# ESP32-Mini-Matrix-Shield-DMA.net
KiCad netlist of a schematic drawn in EAGLE
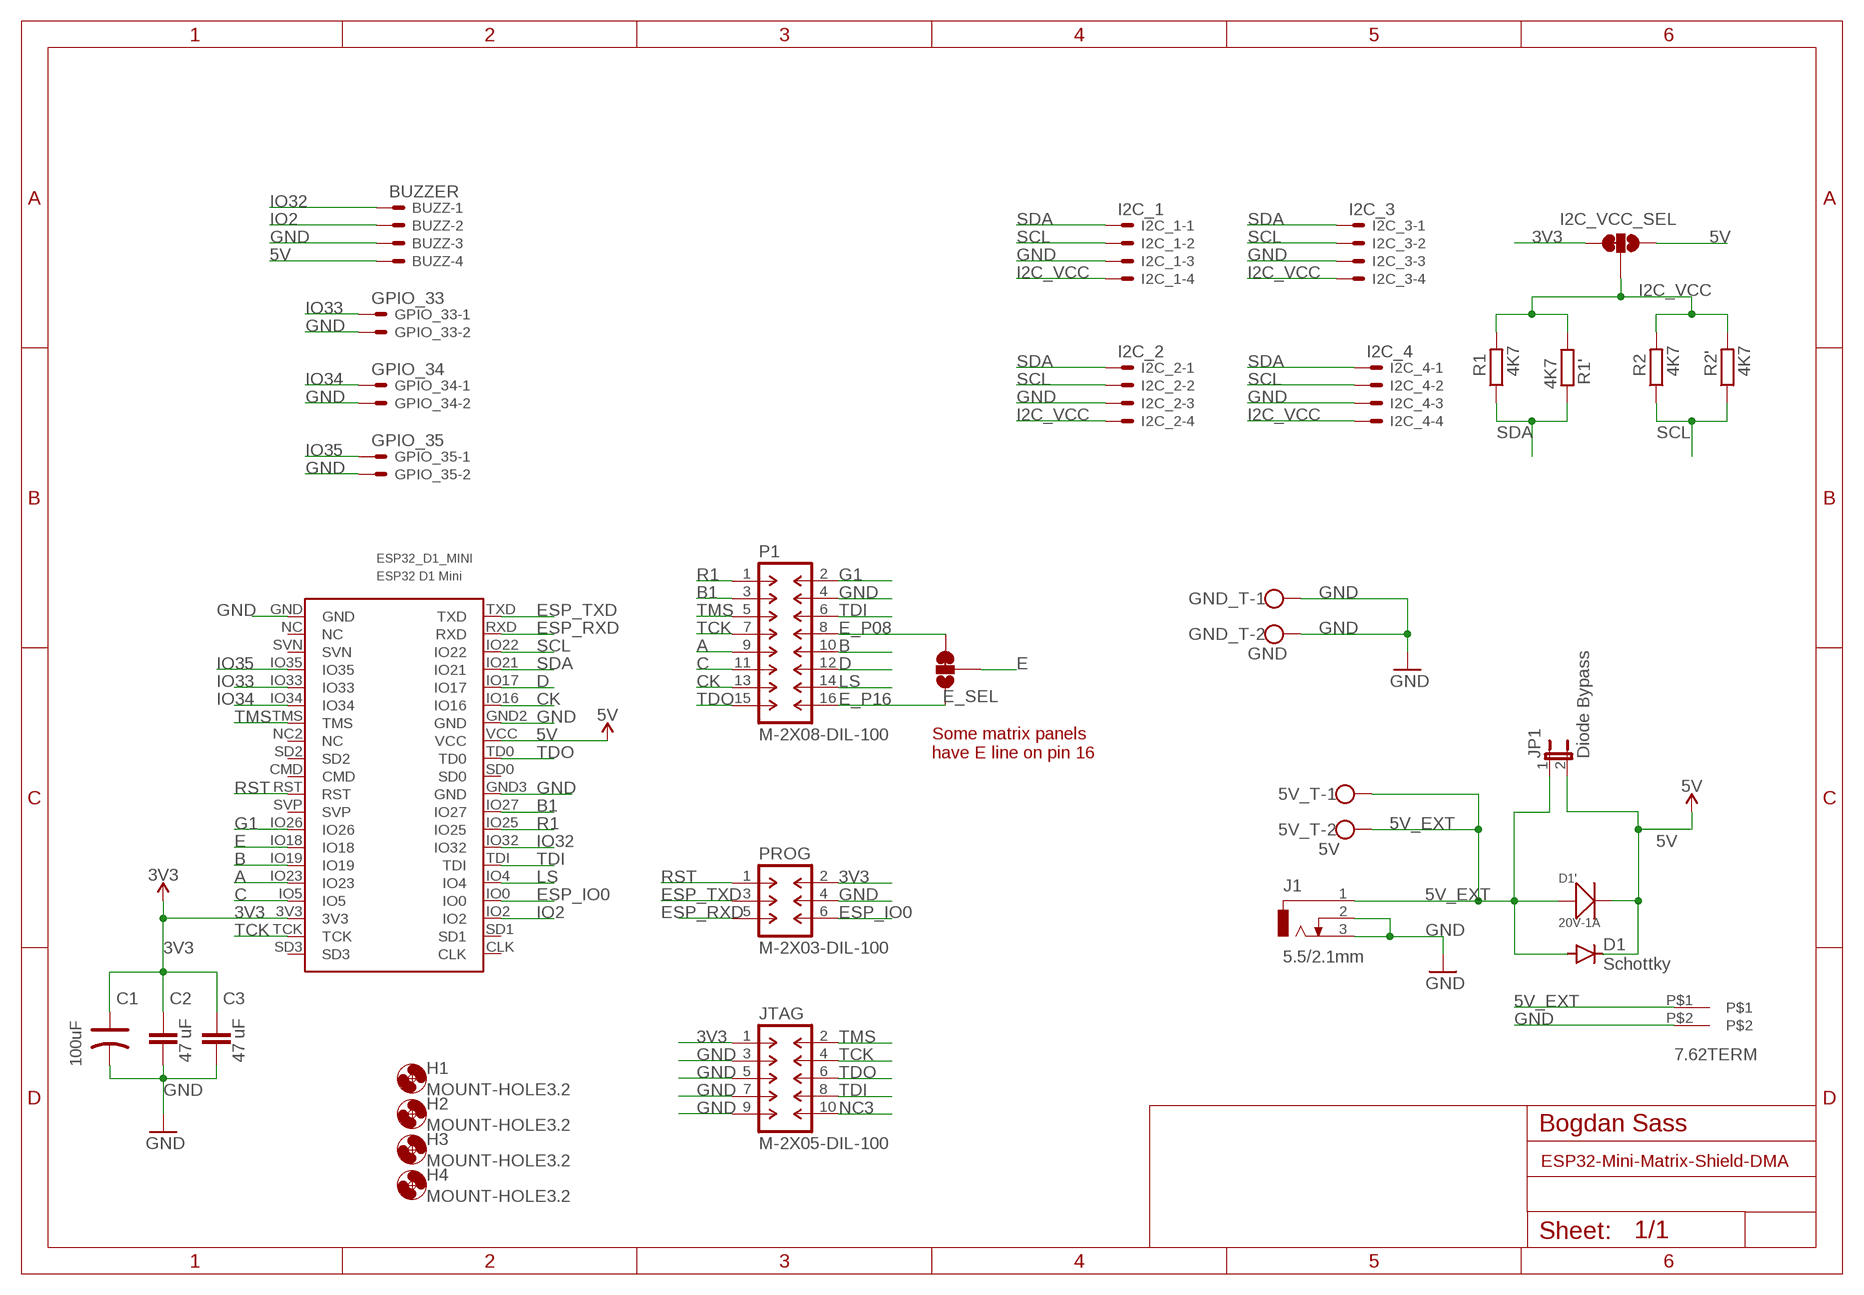
[diagram p0: schematic, sheet 1]

(export (version "E")
  (design (tool "Eeschema 10.0.6"))
  (components
    (comp (ref "5V_T")
      (value "5V")
      (footprint "eagle-import:W237-102")
      (fields (field (name "MPN") "237-102"))
      (libsource (lib "eagle-import") (part "W237-102"))
    )
    (comp (ref "BUZZ")
      (value "BUZZER")
      (footprint "eagle-import:JST-XH-04-PACKAGE-LONG-PAD")
      (libsource (lib "eagle-import") (part "JST-XH-04-PIN-LONG-PAD"))
    )
    (comp (ref "C1")
      (value "100uF")
      (footprint "eagle-import:PC-D5.3MM")
      (fields (field (name "MPN") "KS 100uF/16V"))
      (libsource (lib "eagle-import") (part "DIP-ALUMINUM-47UF-16V(D5-H7MM)"))
    )
    (comp (ref "C2")
      (value "47 uF")
      (footprint "eagle-import:0805-CAP-LARGEPADS")
      (libsource (lib "eagle-import") (part "CAP0805-CAP-LARGEPADS"))
    )
    (comp (ref "C3")
      (value "47 uF")
      (footprint "eagle-import:0805-CAP-LARGEPADS")
      (libsource (lib "eagle-import") (part "CAP0805-CAP-LARGEPADS"))
    )
    (comp (ref "D1")
      (value "Schottky")
      (footprint "eagle-import:DO41-10")
      (libsource (lib "eagle-import") (part "1N4004"))
    )
    (comp (ref "D1'")
      (value "20V-1A")
      (footprint "eagle-import:SOD-123")
      (fields (field (name "MPN") "B5819W"))
      (libsource (lib "eagle-import") (part "SMD-DIODE-SCHOTTKY-20V-1A(SOD-123)"))
    )
    (comp (ref "ESP32_D1_MINI")
      (value "ESP32 D1 Mini")
      (footprint "eagle-import:MH-ET_ESP32_D1_MINI")
      (libsource (lib "eagle-import") (part "MH-ET_ESP32_D1_MINI"))
    )
    (comp (ref "E_SEL")
      (value "JUMPER-SMT_3_1-NC_TRACE_SILK")
      (footprint "eagle-import:SMT-JUMPER_3_1-NC_TRACE_SILK")
      (libsource (lib "eagle-import") (part "JUMPER-SMT_3_1-NC_TRACE_SILK"))
    )
    (comp (ref "GND_T")
      (value "GND")
      (footprint "eagle-import:W237-102")
      (fields (field (name "MPN") "237-102"))
      (libsource (lib "eagle-import") (part "W237-102"))
    )
    (comp (ref "GPIO_33")
      (value "GPIO_33")
      (footprint "eagle-import:JST-XH-02-PACKAGE-LONG-PAD")
      (libsource (lib "eagle-import") (part "JST-XH-02-PIN-LONG-PAD"))
    )
    (comp (ref "GPIO_34")
      (value "GPIO_34")
      (footprint "eagle-import:JST-XH-02-PACKAGE-LONG-PAD")
      (libsource (lib "eagle-import") (part "JST-XH-02-PIN-LONG-PAD"))
    )
    (comp (ref "GPIO_35")
      (value "GPIO_35")
      (footprint "eagle-import:JST-XH-02-PACKAGE-LONG-PAD")
      (libsource (lib "eagle-import") (part "JST-XH-02-PIN-LONG-PAD"))
    )
    (comp (ref "H1")
      (value "MOUNT-HOLE3.2")
      (footprint "eagle-import:3,2")
      (libsource (lib "eagle-import") (part "MOUNT-HOLE3.2"))
    )
    (comp (ref "H2")
      (value "MOUNT-HOLE3.2")
      (footprint "eagle-import:3,2")
      (libsource (lib "eagle-import") (part "MOUNT-HOLE3.2"))
    )
    (comp (ref "H3")
      (value "MOUNT-HOLE3.2")
      (footprint "eagle-import:3,2")
      (libsource (lib "eagle-import") (part "MOUNT-HOLE3.2"))
    )
    (comp (ref "H4")
      (value "MOUNT-HOLE3.2")
      (footprint "eagle-import:3,2")
      (libsource (lib "eagle-import") (part "MOUNT-HOLE3.2"))
    )
    (comp (ref "I2C_1")
      (value "I2C_1")
      (footprint "eagle-import:JST-XH-04-PACKAGE-LONG-PAD")
      (libsource (lib "eagle-import") (part "JST-XH-04-PIN-LONG-PAD"))
    )
    (comp (ref "I2C_2")
      (value "I2C_2")
      (footprint "eagle-import:JST-XH-04-PACKAGE-LONG-PAD")
      (libsource (lib "eagle-import") (part "JST-XH-04-PIN-LONG-PAD"))
    )
    (comp (ref "I2C_3")
      (value "I2C_3")
      (footprint "eagle-import:JST-XH-04-PACKAGE-LONG-PAD")
      (libsource (lib "eagle-import") (part "JST-XH-04-PIN-LONG-PAD"))
    )
    (comp (ref "I2C_4")
      (value "I2C_4")
      (footprint "eagle-import:JST-XH-04-PACKAGE-LONG-PAD")
      (libsource (lib "eagle-import") (part "JST-XH-04-PIN-LONG-PAD"))
    )
    (comp (ref "I2C_VCC_SEL")
      (value "JUMPER-SMT_3_1-NC_TRACE_SILK")
      (footprint "eagle-import:SMT-JUMPER_3_1-NC_TRACE_SILK")
      (libsource (lib "eagle-import") (part "JUMPER-SMT_3_1-NC_TRACE_SILK"))
    )
    (comp (ref "J1")
      (value "5.5/2.1mm")
      (footprint "eagle-import:DCJ0303")
      (libsource (lib "eagle-import") (part "DCJ0303"))
    )
    (comp (ref "JP1")
      (value "Diode Bypass")
      (footprint "eagle-import:JP1")
      (libsource (lib "eagle-import") (part "JP1E"))
    )
    (comp (ref "JTAG")
      (value "M-2X05-DIL-100")
      (footprint "eagle-import:DIL-100-2X05")
      (libsource (lib "eagle-import") (part "M-2X05-DIL-100"))
    )
    (comp (ref "P1")
      (value "M-2X08-DIL-100")
      (footprint "eagle-import:DIL-100-2X08")
      (libsource (lib "eagle-import") (part "M-2X08-DIL-100"))
    )
    (comp (ref "PROG")
      (value "M-2X03-DIL-100")
      (footprint "eagle-import:DIL-100-2X03")
      (libsource (lib "eagle-import") (part "M-2X03-DIL-100"))
    )
    (comp (ref "R1")
      (value "4K7")
      (footprint "eagle-import:0207_10")
      (libsource (lib "eagle-import") (part "R-EU_0207/10"))
    )
    (comp (ref "R1'")
      (value "4K7")
      (footprint "eagle-import:M0805")
      (libsource (lib "eagle-import") (part "R-EU_M0805"))
    )
    (comp (ref "R2")
      (value "4K7")
      (footprint "eagle-import:0207_10")
      (libsource (lib "eagle-import") (part "R-EU_0207/10"))
    )
    (comp (ref "R2'")
      (value "4K7")
      (footprint "eagle-import:M0805")
      (libsource (lib "eagle-import") (part "R-EU_M0805"))
    )
    (comp (ref "ST_01")
      (value "ST_01")
      (footprint "eagle-import:CON-TERM-7.62")
      (libsource (lib "eagle-import") (part "CON-TERM-7.62"))
    )
  )
  (nets
    (net (code "1") (name "/5V_EXT") (class "Default")
      (node (ref "5V_T") (pin "1") (pinfunction "KL_1") (pintype "passive"))
      (node (ref "5V_T") (pin "2") (pinfunction "KL_2") (pintype "passive"))
      (node (ref "D1") (pin "A") (pinfunction "A_A") (pintype "passive"))
      (node (ref "D1'") (pin "+") (pinfunction "+_+") (pintype "passive"))
      (node (ref "J1") (pin "1") (pinfunction "1_1") (pintype "passive"))
      (node (ref "JP1") (pin "1") (pinfunction "1_1") (pintype "passive"))
      (node (ref "ST_01") (pin "P$1") (pinfunction "P$1_P$1") (pintype "bidirectional"))
    )
    (net (code "2") (name "/A") (class "Default")
      (node (ref "ESP32_D1_MINI") (pin "IO23") (pinfunction "IO23_IO23") (pintype "bidirectional"))
      (node (ref "P1") (pin "9") (pinfunction "9_9") (pintype "passive"))
    )
    (net (code "3") (name "/B") (class "Default")
      (node (ref "ESP32_D1_MINI") (pin "IO19") (pinfunction "IO19_IO19") (pintype "bidirectional"))
      (node (ref "P1") (pin "10") (pinfunction "10_10") (pintype "passive"))
    )
    (net (code "4") (name "/B1") (class "Default")
      (node (ref "ESP32_D1_MINI") (pin "IO27") (pinfunction "IO27_IO27") (pintype "bidirectional"))
      (node (ref "P1") (pin "3") (pinfunction "3_3") (pintype "passive"))
    )
    (net (code "5") (name "/C") (class "Default")
      (node (ref "ESP32_D1_MINI") (pin "IO5") (pinfunction "IO5_IO5") (pintype "bidirectional"))
      (node (ref "P1") (pin "11") (pinfunction "11_11") (pintype "passive"))
    )
    (net (code "6") (name "/CK") (class "Default")
      (node (ref "ESP32_D1_MINI") (pin "IO16") (pinfunction "IO16_IO16") (pintype "bidirectional"))
      (node (ref "P1") (pin "13") (pinfunction "13_13") (pintype "passive"))
    )
    (net (code "7") (name "/D") (class "Default")
      (node (ref "ESP32_D1_MINI") (pin "IO17") (pinfunction "IO17_IO17") (pintype "bidirectional"))
      (node (ref "P1") (pin "12") (pinfunction "12_12") (pintype "passive"))
    )
    (net (code "8") (name "/E") (class "Default")
      (node (ref "ESP32_D1_MINI") (pin "IO18") (pinfunction "IO18_IO18") (pintype "bidirectional"))
      (node (ref "E_SEL") (pin "2") (pinfunction "2_2") (pintype "passive"))
    )
    (net (code "9") (name "/ESP_IO0") (class "Default")
      (node (ref "ESP32_D1_MINI") (pin "IO0") (pinfunction "IO0_IO0") (pintype "bidirectional"))
      (node (ref "PROG") (pin "6") (pinfunction "6_6") (pintype "passive"))
    )
    (net (code "10") (name "/ESP_RXD") (class "Default")
      (node (ref "ESP32_D1_MINI") (pin "RXD") (pinfunction "RXD_RXD") (pintype "bidirectional"))
      (node (ref "PROG") (pin "5") (pinfunction "5_5") (pintype "passive"))
    )
    (net (code "11") (name "/ESP_TXD") (class "Default")
      (node (ref "ESP32_D1_MINI") (pin "TXD") (pinfunction "TXD_TXD") (pintype "bidirectional"))
      (node (ref "PROG") (pin "3") (pinfunction "3_3") (pintype "passive"))
    )
    (net (code "12") (name "/E_P08") (class "Default")
      (node (ref "E_SEL") (pin "3") (pinfunction "3_3") (pintype "passive"))
      (node (ref "P1") (pin "8") (pinfunction "8_8") (pintype "passive"))
    )
    (net (code "13") (name "/E_P16") (class "Default")
      (node (ref "E_SEL") (pin "1") (pinfunction "1_1") (pintype "passive"))
      (node (ref "P1") (pin "16") (pinfunction "16_16") (pintype "passive"))
    )
    (net (code "14") (name "/G1") (class "Default")
      (node (ref "ESP32_D1_MINI") (pin "IO26") (pinfunction "IO26_IO26") (pintype "bidirectional"))
      (node (ref "P1") (pin "2") (pinfunction "2_2") (pintype "passive"))
    )
    (net (code "15") (name "/I2C_VCC") (class "Default")
      (node (ref "I2C_1") (pin "4") (pinfunction "S_4") (pintype "passive"))
      (node (ref "I2C_2") (pin "4") (pinfunction "S_4") (pintype "passive"))
      (node (ref "I2C_3") (pin "4") (pinfunction "S_4") (pintype "passive"))
      (node (ref "I2C_4") (pin "4") (pinfunction "S_4") (pintype "passive"))
      (node (ref "I2C_VCC_SEL") (pin "2") (pinfunction "2_2") (pintype "passive"))
      (node (ref "R1") (pin "2") (pinfunction "2_2") (pintype "passive"))
      (node (ref "R1'") (pin "1") (pinfunction "1_1") (pintype "passive"))
      (node (ref "R2") (pin "2") (pinfunction "2_2") (pintype "passive"))
      (node (ref "R2'") (pin "2") (pinfunction "2_2") (pintype "passive"))
    )
    (net (code "16") (name "/IO2") (class "Default")
      (node (ref "BUZZ") (pin "2") (pinfunction "S_2") (pintype "passive"))
      (node (ref "ESP32_D1_MINI") (pin "IO2") (pinfunction "IO2_IO2") (pintype "bidirectional"))
    )
    (net (code "17") (name "/IO32") (class "Default")
      (node (ref "BUZZ") (pin "1") (pinfunction "S_1") (pintype "passive"))
      (node (ref "ESP32_D1_MINI") (pin "IO32") (pinfunction "IO32_IO32") (pintype "bidirectional"))
    )
    (net (code "18") (name "/IO33") (class "Default")
      (node (ref "ESP32_D1_MINI") (pin "IO33") (pinfunction "IO33_IO33") (pintype "bidirectional"))
      (node (ref "GPIO_33") (pin "1") (pinfunction "S_1") (pintype "passive"))
    )
    (net (code "19") (name "/IO34") (class "Default")
      (node (ref "ESP32_D1_MINI") (pin "IO34") (pinfunction "IO34_IO34") (pintype "bidirectional"))
      (node (ref "GPIO_34") (pin "1") (pinfunction "S_1") (pintype "passive"))
    )
    (net (code "20") (name "/IO35") (class "Default")
      (node (ref "ESP32_D1_MINI") (pin "IO35") (pinfunction "IO35_IO35") (pintype "bidirectional"))
      (node (ref "GPIO_35") (pin "1") (pinfunction "S_1") (pintype "passive"))
    )
    (net (code "21") (name "/LS") (class "Default")
      (node (ref "ESP32_D1_MINI") (pin "IO4") (pinfunction "IO4_IO4") (pintype "bidirectional"))
      (node (ref "P1") (pin "14") (pinfunction "14_14") (pintype "passive"))
    )
    (net (code "22") (name "/NC3") (class "Default")
      (node (ref "JTAG") (pin "10") (pinfunction "10_10") (pintype "passive"))
    )
    (net (code "23") (name "/R1") (class "Default")
      (node (ref "ESP32_D1_MINI") (pin "IO25") (pinfunction "IO25_IO25") (pintype "bidirectional"))
      (node (ref "P1") (pin "1") (pinfunction "1_1") (pintype "passive"))
    )
    (net (code "24") (name "/RST") (class "Default")
      (node (ref "ESP32_D1_MINI") (pin "RST") (pinfunction "RST_RST") (pintype "bidirectional"))
      (node (ref "PROG") (pin "1") (pinfunction "1_1") (pintype "passive"))
    )
    (net (code "25") (name "/SCL") (class "Default")
      (node (ref "ESP32_D1_MINI") (pin "IO22") (pinfunction "IO22_IO22") (pintype "bidirectional"))
      (node (ref "I2C_1") (pin "2") (pinfunction "S_2") (pintype "passive"))
      (node (ref "I2C_2") (pin "2") (pinfunction "S_2") (pintype "passive"))
      (node (ref "I2C_3") (pin "2") (pinfunction "S_2") (pintype "passive"))
      (node (ref "I2C_4") (pin "2") (pinfunction "S_2") (pintype "passive"))
      (node (ref "R2") (pin "1") (pinfunction "1_1") (pintype "passive"))
      (node (ref "R2'") (pin "1") (pinfunction "1_1") (pintype "passive"))
    )
    (net (code "26") (name "/SDA") (class "Default")
      (node (ref "ESP32_D1_MINI") (pin "IO21") (pinfunction "IO21_IO21") (pintype "bidirectional"))
      (node (ref "I2C_1") (pin "1") (pinfunction "S_1") (pintype "passive"))
      (node (ref "I2C_2") (pin "1") (pinfunction "S_1") (pintype "passive"))
      (node (ref "I2C_3") (pin "1") (pinfunction "S_1") (pintype "passive"))
      (node (ref "I2C_4") (pin "1") (pinfunction "S_1") (pintype "passive"))
      (node (ref "R1") (pin "1") (pinfunction "1_1") (pintype "passive"))
      (node (ref "R1'") (pin "2") (pinfunction "2_2") (pintype "passive"))
    )
    (net (code "27") (name "/TCK") (class "Default")
      (node (ref "ESP32_D1_MINI") (pin "TCK") (pinfunction "TCK_TCK") (pintype "bidirectional"))
      (node (ref "JTAG") (pin "4") (pinfunction "4_4") (pintype "passive"))
      (node (ref "P1") (pin "7") (pinfunction "7_7") (pintype "passive"))
    )
    (net (code "28") (name "/TDI") (class "Default")
      (node (ref "ESP32_D1_MINI") (pin "TDI") (pinfunction "TDI_TDI") (pintype "bidirectional"))
      (node (ref "JTAG") (pin "8") (pinfunction "8_8") (pintype "passive"))
      (node (ref "P1") (pin "6") (pinfunction "6_6") (pintype "passive"))
    )
    (net (code "29") (name "/TDO") (class "Default")
      (node (ref "ESP32_D1_MINI") (pin "TD0") (pinfunction "TD0_TD0") (pintype "bidirectional"))
      (node (ref "JTAG") (pin "6") (pinfunction "6_6") (pintype "passive"))
      (node (ref "P1") (pin "15") (pinfunction "15_15") (pintype "passive"))
    )
    (net (code "30") (name "/TMS") (class "Default")
      (node (ref "ESP32_D1_MINI") (pin "TMS") (pinfunction "TMS_TMS") (pintype "bidirectional"))
      (node (ref "JTAG") (pin "2") (pinfunction "2_2") (pintype "passive"))
      (node (ref "P1") (pin "5") (pinfunction "5_5") (pintype "passive"))
    )
    (net (code "31") (name "3V3") (class "Default")
      (node (ref "C1") (pin "+") (pinfunction "+_+") (pintype "passive"))
      (node (ref "C2") (pin "1") (pinfunction "1_1") (pintype "passive"))
      (node (ref "C3") (pin "1") (pinfunction "1_1") (pintype "passive"))
      (node (ref "ESP32_D1_MINI") (pin "3V3") (pinfunction "3V3_3V3") (pintype "bidirectional"))
      (node (ref "I2C_VCC_SEL") (pin "3") (pinfunction "3_3") (pintype "passive"))
      (node (ref "JTAG") (pin "1") (pinfunction "1_1") (pintype "passive"))
      (node (ref "PROG") (pin "2") (pinfunction "2_2") (pintype "passive"))
    )
    (net (code "32") (name "5V") (class "Default")
      (node (ref "BUZZ") (pin "4") (pinfunction "S_4") (pintype "passive"))
      (node (ref "D1") (pin "C") (pinfunction "C_C") (pintype "passive"))
      (node (ref "D1'") (pin "-") (pinfunction "-_-") (pintype "passive"))
      (node (ref "ESP32_D1_MINI") (pin "VCC") (pinfunction "VCC_VCC") (pintype "bidirectional"))
      (node (ref "I2C_VCC_SEL") (pin "1") (pinfunction "1_1") (pintype "passive"))
      (node (ref "JP1") (pin "2") (pinfunction "2_2") (pintype "passive"))
    )
    (net (code "33") (name "GND") (class "Default")
      (node (ref "BUZZ") (pin "3") (pinfunction "S_3") (pintype "passive"))
      (node (ref "C1") (pin "-") (pinfunction "-_-") (pintype "passive"))
      (node (ref "C2") (pin "2") (pinfunction "2_2") (pintype "passive"))
      (node (ref "C3") (pin "2") (pinfunction "2_2") (pintype "passive"))
      (node (ref "ESP32_D1_MINI") (pin "GND") (pinfunction "GND_GND") (pintype "bidirectional"))
      (node (ref "ESP32_D1_MINI") (pin "GND2") (pinfunction "GND_GND2") (pintype "bidirectional"))
      (node (ref "ESP32_D1_MINI") (pin "GND3") (pinfunction "GND_GND3") (pintype "bidirectional"))
      (node (ref "GND_T") (pin "1") (pinfunction "KL_1") (pintype "passive"))
      (node (ref "GND_T") (pin "2") (pinfunction "KL_2") (pintype "passive"))
      (node (ref "GPIO_33") (pin "2") (pinfunction "S_2") (pintype "passive"))
      (node (ref "GPIO_34") (pin "2") (pinfunction "S_2") (pintype "passive"))
      (node (ref "GPIO_35") (pin "2") (pinfunction "S_2") (pintype "passive"))
      (node (ref "I2C_1") (pin "3") (pinfunction "S_3") (pintype "passive"))
      (node (ref "I2C_2") (pin "3") (pinfunction "S_3") (pintype "passive"))
      (node (ref "I2C_3") (pin "3") (pinfunction "S_3") (pintype "passive"))
      (node (ref "I2C_4") (pin "3") (pinfunction "S_3") (pintype "passive"))
      (node (ref "J1") (pin "2") (pinfunction "2_2") (pintype "passive"))
      (node (ref "J1") (pin "3") (pinfunction "3_3") (pintype "passive"))
      (node (ref "JTAG") (pin "3") (pinfunction "3_3") (pintype "passive"))
      (node (ref "JTAG") (pin "5") (pinfunction "5_5") (pintype "passive"))
      (node (ref "JTAG") (pin "7") (pinfunction "7_7") (pintype "passive"))
      (node (ref "JTAG") (pin "9") (pinfunction "9_9") (pintype "passive"))
      (node (ref "P1") (pin "4") (pinfunction "4_4") (pintype "passive"))
      (node (ref "PROG") (pin "4") (pinfunction "4_4") (pintype "passive"))
      (node (ref "ST_01") (pin "P$2") (pinfunction "P$2_P$2") (pintype "bidirectional"))
    )
    (net (code "34") (name "unconnected-(ESP32_D1_MINI-NC-PadNC2)") (class "Default")
      (node (ref "ESP32_D1_MINI") (pin "NC2") (pinfunction "NC_NC2") (pintype "bidirectional"))
    )
    (net (code "35") (name "unconnected-(ESP32_D1_MINI-PadCLK)") (class "Default")
      (node (ref "ESP32_D1_MINI") (pin "CLK") (pinfunction "CLK_CLK") (pintype "bidirectional"))
    )
    (net (code "36") (name "unconnected-(ESP32_D1_MINI-PadCMD)") (class "Default")
      (node (ref "ESP32_D1_MINI") (pin "CMD") (pinfunction "CMD_CMD") (pintype "bidirectional"))
    )
    (net (code "37") (name "unconnected-(ESP32_D1_MINI-PadNC)") (class "Default")
      (node (ref "ESP32_D1_MINI") (pin "NC") (pinfunction "NC_NC") (pintype "bidirectional"))
    )
    (net (code "38") (name "unconnected-(ESP32_D1_MINI-PadSD0)") (class "Default")
      (node (ref "ESP32_D1_MINI") (pin "SD0") (pinfunction "SD0_SD0") (pintype "bidirectional"))
    )
    (net (code "39") (name "unconnected-(ESP32_D1_MINI-PadSD1)") (class "Default")
      (node (ref "ESP32_D1_MINI") (pin "SD1") (pinfunction "SD1_SD1") (pintype "bidirectional"))
    )
    (net (code "40") (name "unconnected-(ESP32_D1_MINI-PadSD2)") (class "Default")
      (node (ref "ESP32_D1_MINI") (pin "SD2") (pinfunction "SD2_SD2") (pintype "bidirectional"))
    )
    (net (code "41") (name "unconnected-(ESP32_D1_MINI-PadSD3)") (class "Default")
      (node (ref "ESP32_D1_MINI") (pin "SD3") (pinfunction "SD3_SD3") (pintype "bidirectional"))
    )
    (net (code "42") (name "unconnected-(ESP32_D1_MINI-PadSVN)") (class "Default")
      (node (ref "ESP32_D1_MINI") (pin "SVN") (pinfunction "SVN_SVN") (pintype "bidirectional"))
    )
    (net (code "43") (name "unconnected-(ESP32_D1_MINI-PadSVP)") (class "Default")
      (node (ref "ESP32_D1_MINI") (pin "SVP") (pinfunction "SVP_SVP") (pintype "bidirectional"))
    )
  )
)
